# Risha.net
KiCad netlist of a schematic drawn in EAGLE
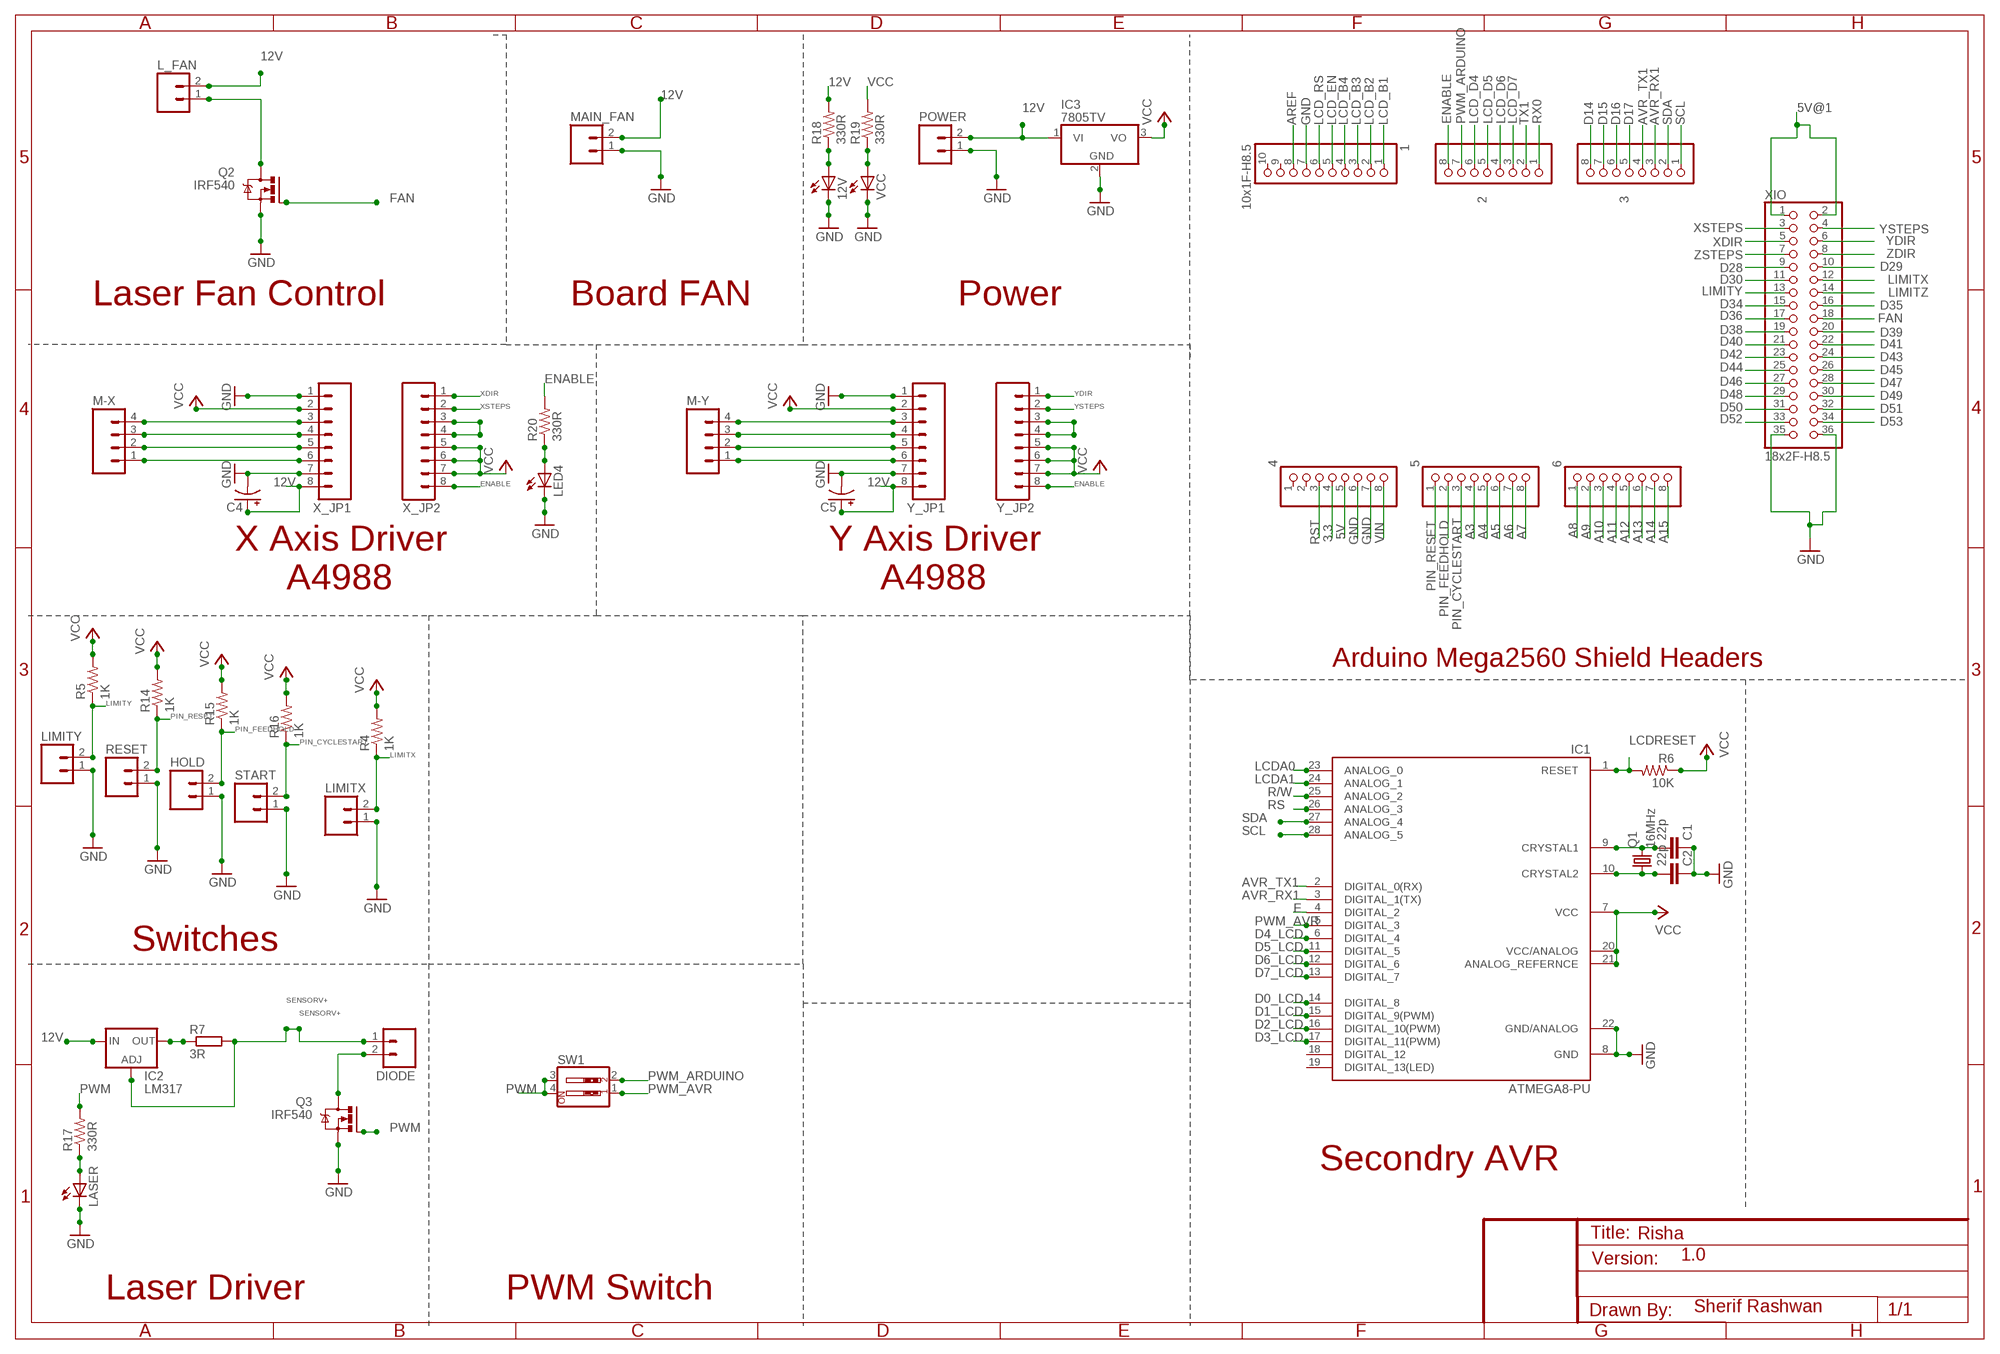
[diagram p0: schematic, sheet 1]

(export (version "E")
  (design (tool "Eeschema 10.0.6"))
  (components
    (comp (ref "1")
      (value "10x1F-H8.5")
      (footprint "eagle-import:1X10")
      (libsource (lib "eagle-import") (part "PINHD-1X10_ARD"))
    )
    (comp (ref "2")
      (value "8x1F-H8.5")
      (footprint "eagle-import:1X08")
      (libsource (lib "eagle-import") (part "PINHD-1X8"))
    )
    (comp (ref "3")
      (value "8x1F-H8.5")
      (footprint "eagle-import:1X08")
      (libsource (lib "eagle-import") (part "PINHD-1X8"))
    )
    (comp (ref "4")
      (value "8x1F-H8.5")
      (footprint "eagle-import:1X08")
      (libsource (lib "eagle-import") (part "PINHD-1X8"))
    )
    (comp (ref "5")
      (value "8x1F-H8.5")
      (footprint "eagle-import:1X08")
      (libsource (lib "eagle-import") (part "PINHD-1X8"))
    )
    (comp (ref "6")
      (value "8x1F-H8.5")
      (footprint "eagle-import:1X08")
      (libsource (lib "eagle-import") (part "PINHD-1X8"))
    )
    (comp (ref "12V")
      (value "LED3MM")
      (footprint "eagle-import:LED3MM")
      (libsource (lib "eagle-import") (part "LED3MM"))
    )
    (comp (ref "C1")
      (value "22p")
      (footprint "eagle-import:C2.5-2")
      (libsource (lib "eagle-import") (part "C2.5/2"))
    )
    (comp (ref "C2")
      (value "22p")
      (footprint "eagle-import:C2.5-2")
      (libsource (lib "eagle-import") (part "C2.5/2"))
    )
    (comp (ref "C4")
      (value "CAP_POLPTH2")
      (footprint "eagle-import:CPOL-RADIAL-10UF-25V")
      (libsource (lib "eagle-import") (part "CAP_POLPTH2"))
    )
    (comp (ref "C5")
      (value "CAP_POLPTH2")
      (footprint "eagle-import:CPOL-RADIAL-10UF-25V")
      (libsource (lib "eagle-import") (part "CAP_POLPTH2"))
    )
    (comp (ref "DIODE")
      (value "M02PTH")
      (footprint "eagle-import:1X02")
      (libsource (lib "eagle-import") (part "M02PTH"))
    )
    (comp (ref "HOLD")
      (value "M02PTH")
      (footprint "eagle-import:1X02")
      (libsource (lib "eagle-import") (part "M02PTH"))
    )
    (comp (ref "IC1")
      (value "ATMEGA8-PU")
      (footprint "eagle-import:DIL28-3")
      (libsource (lib "eagle-import") (part "ATMEGA8-PU"))
    )
    (comp (ref "IC2")
      (value "LM317")
      (footprint "eagle-import:TO3-K02")
      (libsource (lib "eagle-import") (part "LM317-TO3"))
    )
    (comp (ref "IC3")
      (value "7805TV")
      (footprint "eagle-import:TO220V")
      (libsource (lib "eagle-import") (part "78TV05"))
    )
    (comp (ref "LASER")
      (value "LED3MM")
      (footprint "eagle-import:LED3MM")
      (libsource (lib "eagle-import") (part "LED3MM"))
    )
    (comp (ref "LED4")
      (value "LED3MM")
      (footprint "eagle-import:LED3MM")
      (libsource (lib "eagle-import") (part "LED3MM"))
    )
    (comp (ref "LIMITX")
      (value "M02PTH")
      (footprint "eagle-import:1X02")
      (libsource (lib "eagle-import") (part "M02PTH"))
    )
    (comp (ref "LIMITY")
      (value "M02PTH")
      (footprint "eagle-import:1X02")
      (libsource (lib "eagle-import") (part "M02PTH"))
    )
    (comp (ref "L_FAN")
      (value "M02PTH")
      (footprint "eagle-import:1X02")
      (libsource (lib "eagle-import") (part "M02PTH"))
    )
    (comp (ref "M-X")
      (value "M04PTH")
      (footprint "eagle-import:1X04")
      (libsource (lib "eagle-import") (part "M04PTH"))
    )
    (comp (ref "M-Y")
      (value "M04PTH")
      (footprint "eagle-import:1X04")
      (libsource (lib "eagle-import") (part "M04PTH"))
    )
    (comp (ref "MAIN_FAN")
      (value "M02PTH")
      (footprint "eagle-import:1X02")
      (libsource (lib "eagle-import") (part "M02PTH"))
    )
    (comp (ref "POWER")
      (value "M02PTH")
      (footprint "eagle-import:1X02")
      (libsource (lib "eagle-import") (part "M02PTH"))
    )
    (comp (ref "Q1")
      (value "16MHz")
      (footprint "eagle-import:HC49US")
      (libsource (lib "eagle-import") (part "CRYSTALHC49US"))
    )
    (comp (ref "Q2")
      (value "IRF540")
      (footprint "eagle-import:TO220BV")
      (libsource (lib "eagle-import") (part "IRF540"))
    )
    (comp (ref "Q3")
      (value "IRF540")
      (footprint "eagle-import:TO220BV")
      (libsource (lib "eagle-import") (part "IRF540"))
    )
    (comp (ref "R4")
      (value "1K")
      (footprint "eagle-import:1_6W-RES")
      (libsource (lib "eagle-import") (part "RESISTORPTH-1/6W"))
    )
    (comp (ref "R5")
      (value "1K")
      (footprint "eagle-import:1_6W-RES")
      (libsource (lib "eagle-import") (part "RESISTORPTH-1/6W"))
    )
    (comp (ref "R6")
      (value "10K")
      (footprint "eagle-import:1_6W-RES")
      (libsource (lib "eagle-import") (part "RESISTORPTH-1/6W"))
    )
    (comp (ref "R7")
      (value "3R")
      (footprint "eagle-import:0309_12")
      (libsource (lib "eagle-import") (part "R-EU_0309/12"))
    )
    (comp (ref "R14")
      (value "1K")
      (footprint "eagle-import:1_6W-RES")
      (libsource (lib "eagle-import") (part "RESISTORPTH-1/6W"))
    )
    (comp (ref "R15")
      (value "1K")
      (footprint "eagle-import:1_6W-RES")
      (libsource (lib "eagle-import") (part "RESISTORPTH-1/6W"))
    )
    (comp (ref "R16")
      (value "1K")
      (footprint "eagle-import:1_6W-RES")
      (libsource (lib "eagle-import") (part "RESISTORPTH-1/6W"))
    )
    (comp (ref "R17")
      (value "330R")
      (footprint "eagle-import:1_6W-RES")
      (libsource (lib "eagle-import") (part "RESISTORPTH-1/6W"))
    )
    (comp (ref "R18")
      (value "330R")
      (footprint "eagle-import:1_6W-RES")
      (libsource (lib "eagle-import") (part "RESISTORPTH-1/6W"))
    )
    (comp (ref "R19")
      (value "330R")
      (footprint "eagle-import:1_6W-RES")
      (libsource (lib "eagle-import") (part "RESISTORPTH-1/6W"))
    )
    (comp (ref "R20")
      (value "330R")
      (footprint "eagle-import:1_6W-RES")
      (libsource (lib "eagle-import") (part "RESISTORPTH-1/6W"))
    )
    (comp (ref "RESET")
      (value "M02PTH")
      (footprint "eagle-import:1X02")
      (libsource (lib "eagle-import") (part "M02PTH"))
    )
    (comp (ref "START")
      (value "M02PTH")
      (footprint "eagle-import:1X02")
      (libsource (lib "eagle-import") (part "M02PTH"))
    )
    (comp (ref "SW1")
      (value "SW_DIP-2")
      (footprint "eagle-import:EDG-02")
      (libsource (lib "eagle-import") (part "SW_DIP-2"))
    )
    (comp (ref "VCC")
      (value "LED3MM")
      (footprint "eagle-import:LED3MM")
      (libsource (lib "eagle-import") (part "LED3MM"))
    )
    (comp (ref "XIO")
      (value "18x2F-H8.5")
      (footprint "eagle-import:2X18")
      (libsource (lib "eagle-import") (part "PINHD-2X18"))
    )
    (comp (ref "X_JP1")
      (value "M08")
      (footprint "eagle-import:1X08")
      (libsource (lib "eagle-import") (part "M08"))
    )
    (comp (ref "X_JP2")
      (value "M08")
      (footprint "eagle-import:1X08")
      (libsource (lib "eagle-import") (part "M08"))
    )
    (comp (ref "Y_JP1")
      (value "M08")
      (footprint "eagle-import:1X08")
      (libsource (lib "eagle-import") (part "M08"))
    )
    (comp (ref "Y_JP2")
      (value "M08")
      (footprint "eagle-import:1X08")
      (libsource (lib "eagle-import") (part "M08"))
    )
  )
  (nets
    (net (code "1") (name "/3.3") (class "Default")
      (node (ref "4") (pin "4") (pinfunction "4_4") (pintype "passive"))
    )
    (net (code "2") (name "/5V") (class "Default")
      (node (ref "4") (pin "5") (pinfunction "5_5") (pintype "passive"))
    )
    (net (code "3") (name "/5V@1") (class "Default")
      (node (ref "XIO") (pin "1") (pinfunction "1_1") (pintype "passive"))
      (node (ref "XIO") (pin "2") (pinfunction "2_2") (pintype "passive"))
    )
    (net (code "4") (name "/12V") (class "Default")
      (node (ref "C4") (pin "1") (pinfunction "+_1") (pintype "passive"))
      (node (ref "C5") (pin "1") (pinfunction "+_1") (pintype "passive"))
      (node (ref "IC2") (pin "1") (pinfunction "IN_1") (pintype "input"))
      (node (ref "IC3") (pin "1") (pinfunction "VI_1") (pintype "input"))
      (node (ref "L_FAN") (pin "2") (pinfunction "2_2") (pintype "passive"))
      (node (ref "MAIN_FAN") (pin "2") (pinfunction "2_2") (pintype "passive"))
      (node (ref "POWER") (pin "2") (pinfunction "2_2") (pintype "passive"))
      (node (ref "R18") (pin "2") (pinfunction "2_2") (pintype "passive"))
      (node (ref "X_JP1") (pin "8") (pinfunction "8_8") (pintype "passive"))
      (node (ref "Y_JP1") (pin "8") (pinfunction "8_8") (pintype "passive"))
    )
    (net (code "5") (name "/A3") (class "Default")
      (node (ref "5") (pin "4") (pinfunction "4_4") (pintype "passive"))
    )
    (net (code "6") (name "/A4") (class "Default")
      (node (ref "5") (pin "5") (pinfunction "5_5") (pintype "passive"))
    )
    (net (code "7") (name "/A5") (class "Default")
      (node (ref "5") (pin "6") (pinfunction "6_6") (pintype "passive"))
    )
    (net (code "8") (name "/A6") (class "Default")
      (node (ref "5") (pin "7") (pinfunction "7_7") (pintype "passive"))
    )
    (net (code "9") (name "/A7") (class "Default")
      (node (ref "5") (pin "8") (pinfunction "8_8") (pintype "passive"))
    )
    (net (code "10") (name "/A8") (class "Default")
      (node (ref "6") (pin "1") (pinfunction "1_1") (pintype "passive"))
    )
    (net (code "11") (name "/A9") (class "Default")
      (node (ref "6") (pin "2") (pinfunction "2_2") (pintype "passive"))
    )
    (net (code "12") (name "/A10") (class "Default")
      (node (ref "6") (pin "3") (pinfunction "3_3") (pintype "passive"))
    )
    (net (code "13") (name "/A11") (class "Default")
      (node (ref "6") (pin "4") (pinfunction "4_4") (pintype "passive"))
    )
    (net (code "14") (name "/A12") (class "Default")
      (node (ref "6") (pin "5") (pinfunction "5_5") (pintype "passive"))
    )
    (net (code "15") (name "/A13") (class "Default")
      (node (ref "6") (pin "6") (pinfunction "6_6") (pintype "passive"))
    )
    (net (code "16") (name "/A14") (class "Default")
      (node (ref "6") (pin "7") (pinfunction "7_7") (pintype "passive"))
    )
    (net (code "17") (name "/A15") (class "Default")
      (node (ref "6") (pin "8") (pinfunction "8_8") (pintype "passive"))
    )
    (net (code "18") (name "/AREF") (class "Default")
      (node (ref "1") (pin "8") (pinfunction "8_8") (pintype "passive"))
    )
    (net (code "19") (name "/AVR_RX1") (class "Default")
      (node (ref "3") (pin "3") (pinfunction "3_3") (pintype "passive"))
      (node (ref "IC1") (pin "3") (pinfunction "DIGITAL_1(TX)_3") (pintype "bidirectional"))
    )
    (net (code "20") (name "/AVR_TX1") (class "Default")
      (node (ref "3") (pin "4") (pinfunction "4_4") (pintype "passive"))
      (node (ref "IC1") (pin "2") (pinfunction "DIGITAL_0(RX)_2") (pintype "bidirectional"))
    )
    (net (code "21") (name "/D0_LCD") (class "Default")
      (node (ref "IC1") (pin "14") (pinfunction "DIGITAL_8_14") (pintype "bidirectional"))
    )
    (net (code "22") (name "/D1_LCD") (class "Default")
      (node (ref "IC1") (pin "15") (pinfunction "DIGITAL_9(PWM)_15") (pintype "bidirectional"))
    )
    (net (code "23") (name "/D2_LCD") (class "Default")
      (node (ref "IC1") (pin "16") (pinfunction "DIGITAL_10(PWM)_16") (pintype "bidirectional"))
    )
    (net (code "24") (name "/D3_LCD") (class "Default")
      (node (ref "IC1") (pin "17") (pinfunction "DIGITAL_11(PWM)_17") (pintype "bidirectional"))
    )
    (net (code "25") (name "/D4_LCD") (class "Default")
      (node (ref "IC1") (pin "6") (pinfunction "DIGITAL_4_6") (pintype "bidirectional"))
    )
    (net (code "26") (name "/D5_LCD") (class "Default")
      (node (ref "IC1") (pin "11") (pinfunction "DIGITAL_5_11") (pintype "bidirectional"))
    )
    (net (code "27") (name "/D6_LCD") (class "Default")
      (node (ref "IC1") (pin "12") (pinfunction "DIGITAL_6_12") (pintype "bidirectional"))
    )
    (net (code "28") (name "/D7_LCD") (class "Default")
      (node (ref "IC1") (pin "13") (pinfunction "DIGITAL_7_13") (pintype "bidirectional"))
    )
    (net (code "29") (name "/D14") (class "Default")
      (node (ref "3") (pin "8") (pinfunction "8_8") (pintype "passive"))
    )
    (net (code "30") (name "/D15") (class "Default")
      (node (ref "3") (pin "7") (pinfunction "7_7") (pintype "passive"))
    )
    (net (code "31") (name "/D16") (class "Default")
      (node (ref "3") (pin "6") (pinfunction "6_6") (pintype "passive"))
    )
    (net (code "32") (name "/D17") (class "Default")
      (node (ref "3") (pin "5") (pinfunction "5_5") (pintype "passive"))
    )
    (net (code "33") (name "/D28") (class "Default")
      (node (ref "XIO") (pin "9") (pinfunction "9_9") (pintype "passive"))
    )
    (net (code "34") (name "/D29") (class "Default")
      (node (ref "XIO") (pin "10") (pinfunction "10_10") (pintype "passive"))
    )
    (net (code "35") (name "/D30") (class "Default")
      (node (ref "XIO") (pin "11") (pinfunction "11_11") (pintype "passive"))
    )
    (net (code "36") (name "/D34") (class "Default")
      (node (ref "XIO") (pin "15") (pinfunction "15_15") (pintype "passive"))
    )
    (net (code "37") (name "/D35") (class "Default")
      (node (ref "XIO") (pin "16") (pinfunction "16_16") (pintype "passive"))
    )
    (net (code "38") (name "/D36") (class "Default")
      (node (ref "XIO") (pin "17") (pinfunction "17_17") (pintype "passive"))
    )
    (net (code "39") (name "/D38") (class "Default")
      (node (ref "XIO") (pin "19") (pinfunction "19_19") (pintype "passive"))
    )
    (net (code "40") (name "/D39") (class "Default")
      (node (ref "XIO") (pin "20") (pinfunction "20_20") (pintype "passive"))
    )
    (net (code "41") (name "/D40") (class "Default")
      (node (ref "XIO") (pin "21") (pinfunction "21_21") (pintype "passive"))
    )
    (net (code "42") (name "/D41") (class "Default")
      (node (ref "XIO") (pin "22") (pinfunction "22_22") (pintype "passive"))
    )
    (net (code "43") (name "/D42") (class "Default")
      (node (ref "XIO") (pin "23") (pinfunction "23_23") (pintype "passive"))
    )
    (net (code "44") (name "/D43") (class "Default")
      (node (ref "XIO") (pin "24") (pinfunction "24_24") (pintype "passive"))
    )
    (net (code "45") (name "/D44") (class "Default")
      (node (ref "XIO") (pin "25") (pinfunction "25_25") (pintype "passive"))
    )
    (net (code "46") (name "/D45") (class "Default")
      (node (ref "XIO") (pin "26") (pinfunction "26_26") (pintype "passive"))
    )
    (net (code "47") (name "/D46") (class "Default")
      (node (ref "XIO") (pin "27") (pinfunction "27_27") (pintype "passive"))
    )
    (net (code "48") (name "/D47") (class "Default")
      (node (ref "XIO") (pin "28") (pinfunction "28_28") (pintype "passive"))
    )
    (net (code "49") (name "/D48") (class "Default")
      (node (ref "XIO") (pin "29") (pinfunction "29_29") (pintype "passive"))
    )
    (net (code "50") (name "/D49") (class "Default")
      (node (ref "XIO") (pin "30") (pinfunction "30_30") (pintype "passive"))
    )
    (net (code "51") (name "/D50") (class "Default")
      (node (ref "XIO") (pin "31") (pinfunction "31_31") (pintype "passive"))
    )
    (net (code "52") (name "/D51") (class "Default")
      (node (ref "XIO") (pin "32") (pinfunction "32_32") (pintype "passive"))
    )
    (net (code "53") (name "/D52") (class "Default")
      (node (ref "XIO") (pin "33") (pinfunction "33_33") (pintype "passive"))
    )
    (net (code "54") (name "/D53") (class "Default")
      (node (ref "XIO") (pin "34") (pinfunction "34_34") (pintype "passive"))
    )
    (net (code "55") (name "/E") (class "Default")
      (node (ref "IC1") (pin "4") (pinfunction "DIGITAL_2_4") (pintype "bidirectional"))
    )
    (net (code "56") (name "/ENABLE") (class "Default")
      (node (ref "2") (pin "8") (pinfunction "8_8") (pintype "passive"))
      (node (ref "R20") (pin "2") (pinfunction "2_2") (pintype "passive"))
      (node (ref "X_JP2") (pin "8") (pinfunction "8_8") (pintype "passive"))
      (node (ref "Y_JP2") (pin "8") (pinfunction "8_8") (pintype "passive"))
    )
    (net (code "57") (name "/FAN") (class "Default")
      (node (ref "Q2") (pin "G") (pinfunction "G_G") (pintype "passive"))
      (node (ref "XIO") (pin "18") (pinfunction "18_18") (pintype "passive"))
    )
    (net (code "58") (name "/LCDA0") (class "Default")
      (node (ref "IC1") (pin "23") (pinfunction "ANALOG_0_23") (pintype "bidirectional"))
    )
    (net (code "59") (name "/LCDA1") (class "Default")
      (node (ref "IC1") (pin "24") (pinfunction "ANALOG_1_24") (pintype "bidirectional"))
    )
    (net (code "60") (name "/LCDRESET") (class "Default")
      (node (ref "IC1") (pin "1") (pinfunction "RESET_1") (pintype "bidirectional"))
      (node (ref "R6") (pin "2") (pinfunction "2_2") (pintype "passive"))
    )
    (net (code "61") (name "/LCD_B1") (class "Default")
      (node (ref "1") (pin "1") (pinfunction "1_1") (pintype "passive"))
    )
    (net (code "62") (name "/LCD_B2") (class "Default")
      (node (ref "1") (pin "2") (pinfunction "2_2") (pintype "passive"))
    )
    (net (code "63") (name "/LCD_B3") (class "Default")
      (node (ref "1") (pin "3") (pinfunction "3_3") (pintype "passive"))
    )
    (net (code "64") (name "/LCD_B4") (class "Default")
      (node (ref "1") (pin "4") (pinfunction "4_4") (pintype "passive"))
    )
    (net (code "65") (name "/LCD_D4") (class "Default")
      (node (ref "2") (pin "6") (pinfunction "6_6") (pintype "passive"))
    )
    (net (code "66") (name "/LCD_D5") (class "Default")
      (node (ref "2") (pin "5") (pinfunction "5_5") (pintype "passive"))
    )
    (net (code "67") (name "/LCD_D6") (class "Default")
      (node (ref "2") (pin "4") (pinfunction "4_4") (pintype "passive"))
    )
    (net (code "68") (name "/LCD_D7") (class "Default")
      (node (ref "2") (pin "3") (pinfunction "3_3") (pintype "passive"))
    )
    (net (code "69") (name "/LCD_EN") (class "Default")
      (node (ref "1") (pin "5") (pinfunction "5_5") (pintype "passive"))
    )
    (net (code "70") (name "/LCD_RS") (class "Default")
      (node (ref "1") (pin "6") (pinfunction "6_6") (pintype "passive"))
    )
    (net (code "71") (name "/LIMITX") (class "Default")
      (node (ref "LIMITX") (pin "2") (pinfunction "2_2") (pintype "passive"))
      (node (ref "R4") (pin "1") (pinfunction "1_1") (pintype "passive"))
      (node (ref "XIO") (pin "12") (pinfunction "12_12") (pintype "passive"))
    )
    (net (code "72") (name "/LIMITY") (class "Default")
      (node (ref "LIMITY") (pin "2") (pinfunction "2_2") (pintype "passive"))
      (node (ref "R5") (pin "1") (pinfunction "1_1") (pintype "passive"))
      (node (ref "XIO") (pin "13") (pinfunction "13_13") (pintype "passive"))
    )
    (net (code "73") (name "/LIMITZ") (class "Default")
      (node (ref "XIO") (pin "14") (pinfunction "14_14") (pintype "passive"))
    )
    (net (code "74") (name "/PIN_CYCLESTART") (class "Default")
      (node (ref "5") (pin "3") (pinfunction "3_3") (pintype "passive"))
      (node (ref "R16") (pin "1") (pinfunction "1_1") (pintype "passive"))
      (node (ref "START") (pin "2") (pinfunction "2_2") (pintype "passive"))
    )
    (net (code "75") (name "/PIN_FEEDHOLD") (class "Default")
      (node (ref "5") (pin "2") (pinfunction "2_2") (pintype "passive"))
      (node (ref "HOLD") (pin "2") (pinfunction "2_2") (pintype "passive"))
      (node (ref "R15") (pin "1") (pinfunction "1_1") (pintype "passive"))
    )
    (net (code "76") (name "/PIN_RESET") (class "Default")
      (node (ref "5") (pin "1") (pinfunction "1_1") (pintype "passive"))
      (node (ref "R14") (pin "1") (pinfunction "1_1") (pintype "passive"))
      (node (ref "RESET") (pin "2") (pinfunction "2_2") (pintype "passive"))
    )
    (net (code "77") (name "/PWM") (class "Default")
      (node (ref "Q3") (pin "G") (pinfunction "G_G") (pintype "passive"))
      (node (ref "R17") (pin "2") (pinfunction "2_2") (pintype "passive"))
      (node (ref "SW1") (pin "3") (pinfunction "3_3") (pintype "passive"))
      (node (ref "SW1") (pin "4") (pinfunction "4_4") (pintype "passive"))
    )
    (net (code "78") (name "/PWM_ARDUINO") (class "Default")
      (node (ref "2") (pin "7") (pinfunction "7_7") (pintype "passive"))
      (node (ref "SW1") (pin "2") (pinfunction "2_2") (pintype "passive"))
    )
    (net (code "79") (name "/PWM_AVR") (class "Default")
      (node (ref "IC1") (pin "5") (pinfunction "DIGITAL_3_5") (pintype "bidirectional"))
      (node (ref "SW1") (pin "1") (pinfunction "1_1") (pintype "passive"))
    )
    (net (code "80") (name "/RS") (class "Default")
      (node (ref "IC1") (pin "26") (pinfunction "ANALOG_3_26") (pintype "bidirectional"))
    )
    (net (code "81") (name "/RST") (class "Default")
      (node (ref "4") (pin "3") (pinfunction "3_3") (pintype "passive"))
    )
    (net (code "82") (name "/RX0") (class "Default")
      (node (ref "2") (pin "1") (pinfunction "1_1") (pintype "passive"))
    )
    (net (code "83") (name "/R{slash}W") (class "Default")
      (node (ref "IC1") (pin "25") (pinfunction "ANALOG_2_25") (pintype "bidirectional"))
    )
    (net (code "84") (name "/SCL") (class "Default")
      (node (ref "3") (pin "1") (pinfunction "1_1") (pintype "passive"))
      (node (ref "IC1") (pin "28") (pinfunction "ANALOG_5_28") (pintype "bidirectional"))
    )
    (net (code "85") (name "/SDA") (class "Default")
      (node (ref "3") (pin "2") (pinfunction "2_2") (pintype "passive"))
      (node (ref "IC1") (pin "27") (pinfunction "ANALOG_4_27") (pintype "bidirectional"))
    )
    (net (code "86") (name "/SENSORV+") (class "Default")
      (node (ref "DIODE") (pin "1") (pinfunction "1_1") (pintype "passive"))
      (node (ref "IC2") (pin "2") (pinfunction "ADJ_2") (pintype "input"))
      (node (ref "R7") (pin "2") (pinfunction "2_2") (pintype "passive"))
    )
    (net (code "87") (name "/TX1") (class "Default")
      (node (ref "2") (pin "2") (pinfunction "2_2") (pintype "passive"))
    )
    (net (code "88") (name "/VIN") (class "Default")
      (node (ref "4") (pin "8") (pinfunction "8_8") (pintype "passive"))
    )
    (net (code "89") (name "/XDIR") (class "Default")
      (node (ref "XIO") (pin "5") (pinfunction "5_5") (pintype "passive"))
      (node (ref "X_JP2") (pin "1") (pinfunction "1_1") (pintype "passive"))
    )
    (net (code "90") (name "/XSTEPS") (class "Default")
      (node (ref "XIO") (pin "3") (pinfunction "3_3") (pintype "passive"))
      (node (ref "X_JP2") (pin "2") (pinfunction "2_2") (pintype "passive"))
    )
    (net (code "91") (name "/YDIR") (class "Default")
      (node (ref "XIO") (pin "6") (pinfunction "6_6") (pintype "passive"))
      (node (ref "Y_JP2") (pin "1") (pinfunction "1_1") (pintype "passive"))
    )
    (net (code "92") (name "/YSTEPS") (class "Default")
      (node (ref "XIO") (pin "4") (pinfunction "4_4") (pintype "passive"))
      (node (ref "Y_JP2") (pin "2") (pinfunction "2_2") (pintype "passive"))
    )
    (net (code "93") (name "/ZDIR") (class "Default")
      (node (ref "XIO") (pin "8") (pinfunction "8_8") (pintype "passive"))
    )
    (net (code "94") (name "/ZSTEPS") (class "Default")
      (node (ref "XIO") (pin "7") (pinfunction "7_7") (pintype "passive"))
    )
    (net (code "95") (name "GND") (class "Default")
      (node (ref "1") (pin "7") (pinfunction "7_7") (pintype "passive"))
      (node (ref "12V") (pin "K") (pinfunction "C_K") (pintype "passive"))
      (node (ref "4") (pin "6") (pinfunction "6_6") (pintype "passive"))
      (node (ref "4") (pin "7") (pinfunction "7_7") (pintype "passive"))
      (node (ref "C1") (pin "1") (pinfunction "1_1") (pintype "passive"))
      (node (ref "C2") (pin "1") (pinfunction "1_1") (pintype "passive"))
      (node (ref "C4") (pin "2") (pinfunction "-_2") (pintype "passive"))
      (node (ref "C5") (pin "2") (pinfunction "-_2") (pintype "passive"))
      (node (ref "HOLD") (pin "1") (pinfunction "1_1") (pintype "passive"))
      (node (ref "IC1") (pin "22") (pinfunction "GND/ANALOG_22") (pintype "power_in"))
      (node (ref "IC1") (pin "8") (pinfunction "GND_8") (pintype "power_in"))
      (node (ref "IC3") (pin "2") (pinfunction "GND_2") (pintype "passive"))
      (node (ref "LASER") (pin "K") (pinfunction "C_K") (pintype "passive"))
      (node (ref "LED4") (pin "K") (pinfunction "C_K") (pintype "passive"))
      (node (ref "LIMITX") (pin "1") (pinfunction "1_1") (pintype "passive"))
      (node (ref "LIMITY") (pin "1") (pinfunction "1_1") (pintype "passive"))
      (node (ref "MAIN_FAN") (pin "1") (pinfunction "1_1") (pintype "passive"))
      (node (ref "POWER") (pin "1") (pinfunction "1_1") (pintype "passive"))
      (node (ref "Q2") (pin "S") (pinfunction "S_S") (pintype "passive"))
      (node (ref "Q3") (pin "S") (pinfunction "S_S") (pintype "passive"))
      (node (ref "RESET") (pin "1") (pinfunction "1_1") (pintype "passive"))
      (node (ref "START") (pin "1") (pinfunction "1_1") (pintype "passive"))
      (node (ref "VCC") (pin "K") (pinfunction "C_K") (pintype "passive"))
      (node (ref "XIO") (pin "35") (pinfunction "35_35") (pintype "passive"))
      (node (ref "XIO") (pin "36") (pinfunction "36_36") (pintype "passive"))
      (node (ref "X_JP1") (pin "1") (pinfunction "1_1") (pintype "passive"))
      (node (ref "X_JP1") (pin "7") (pinfunction "7_7") (pintype "passive"))
      (node (ref "Y_JP1") (pin "1") (pinfunction "1_1") (pintype "passive"))
      (node (ref "Y_JP1") (pin "7") (pinfunction "7_7") (pintype "passive"))
    )
    (net (code "96") (name "Net-(12V-PadA)") (class "Default")
      (node (ref "12V") (pin "A") (pinfunction "A_A") (pintype "passive"))
      (node (ref "R18") (pin "1") (pinfunction "1_1") (pintype "passive"))
    )
    (net (code "97") (name "Net-(DIODE-Pad2)") (class "Default")
      (node (ref "DIODE") (pin "2") (pinfunction "2_2") (pintype "passive"))
      (node (ref "Q3") (pin "D") (pinfunction "D_D") (pintype "passive"))
    )
    (net (code "98") (name "Net-(IC1-CRYSTAL1)") (class "Default")
      (node (ref "C1") (pin "2") (pinfunction "2_2") (pintype "passive"))
      (node (ref "IC1") (pin "9") (pinfunction "CRYSTAL1_9") (pintype "bidirectional"))
      (node (ref "Q1") (pin "2") (pinfunction "2_2") (pintype "passive"))
    )
    (net (code "99") (name "Net-(IC1-CRYSTAL2)") (class "Default")
      (node (ref "C2") (pin "2") (pinfunction "2_2") (pintype "passive"))
      (node (ref "IC1") (pin "10") (pinfunction "CRYSTAL2_10") (pintype "bidirectional"))
      (node (ref "Q1") (pin "1") (pinfunction "1_1") (pintype "passive"))
    )
    (net (code "100") (name "Net-(IC2-OUT)") (class "Default")
      (node (ref "IC2") (pin "3") (pinfunction "OUT_3") (pintype "passive"))
      (node (ref "R7") (pin "1") (pinfunction "1_1") (pintype "passive"))
    )
    (net (code "101") (name "Net-(LASER-PadA)") (class "Default")
      (node (ref "LASER") (pin "A") (pinfunction "A_A") (pintype "passive"))
      (node (ref "R17") (pin "1") (pinfunction "1_1") (pintype "passive"))
    )
    (net (code "102") (name "Net-(LED4-PadA)") (class "Default")
      (node (ref "LED4") (pin "A") (pinfunction "A_A") (pintype "passive"))
      (node (ref "R20") (pin "1") (pinfunction "1_1") (pintype "passive"))
    )
    (net (code "103") (name "Net-(L_FAN-Pad1)") (class "Default")
      (node (ref "L_FAN") (pin "1") (pinfunction "1_1") (pintype "passive"))
      (node (ref "Q2") (pin "D") (pinfunction "D_D") (pintype "passive"))
    )
    (net (code "104") (name "Net-(M-X-Pad1)") (class "Default")
      (node (ref "M-X") (pin "1") (pinfunction "1_1") (pintype "passive"))
      (node (ref "X_JP1") (pin "6") (pinfunction "6_6") (pintype "passive"))
    )
    (net (code "105") (name "Net-(M-X-Pad2)") (class "Default")
      (node (ref "M-X") (pin "2") (pinfunction "2_2") (pintype "passive"))
      (node (ref "X_JP1") (pin "5") (pinfunction "5_5") (pintype "passive"))
    )
    (net (code "106") (name "Net-(M-X-Pad3)") (class "Default")
      (node (ref "M-X") (pin "3") (pinfunction "3_3") (pintype "passive"))
      (node (ref "X_JP1") (pin "4") (pinfunction "4_4") (pintype "passive"))
    )
    (net (code "107") (name "Net-(M-X-Pad4)") (class "Default")
      (node (ref "M-X") (pin "4") (pinfunction "4_4") (pintype "passive"))
      (node (ref "X_JP1") (pin "3") (pinfunction "3_3") (pintype "passive"))
    )
    (net (code "108") (name "Net-(M-Y-Pad1)") (class "Default")
      (node (ref "M-Y") (pin "1") (pinfunction "1_1") (pintype "passive"))
      (node (ref "Y_JP1") (pin "6") (pinfunction "6_6") (pintype "passive"))
    )
    (net (code "109") (name "Net-(M-Y-Pad2)") (class "Default")
      (node (ref "M-Y") (pin "2") (pinfunction "2_2") (pintype "passive"))
      (node (ref "Y_JP1") (pin "5") (pinfunction "5_5") (pintype "passive"))
    )
    (net (code "110") (name "Net-(M-Y-Pad3)") (class "Default")
      (node (ref "M-Y") (pin "3") (pinfunction "3_3") (pintype "passive"))
      (node (ref "Y_JP1") (pin "4") (pinfunction "4_4") (pintype "passive"))
    )
    (net (code "111") (name "Net-(M-Y-Pad4)") (class "Default")
      (node (ref "M-Y") (pin "4") (pinfunction "4_4") (pintype "passive"))
      (node (ref "Y_JP1") (pin "3") (pinfunction "3_3") (pintype "passive"))
    )
    (net (code "112") (name "Net-(R19-Pad1)") (class "Default")
      (node (ref "R19") (pin "1") (pinfunction "1_1") (pintype "passive"))
      (node (ref "VCC") (pin "A") (pinfunction "A_A") (pintype "passive"))
    )
    (net (code "113") (name "Net-(X_JP2-Pad3)") (class "Default")
      (node (ref "X_JP2") (pin "3") (pinfunction "3_3") (pintype "passive"))
      (node (ref "X_JP2") (pin "4") (pinfunction "4_4") (pintype "passive"))
    )
    (net (code "114") (name "Net-(Y_JP2-Pad3)") (class "Default")
      (node (ref "Y_JP2") (pin "3") (pinfunction "3_3") (pintype "passive"))
      (node (ref "Y_JP2") (pin "4") (pinfunction "4_4") (pintype "passive"))
    )
    (net (code "115") (name "VCC") (class "Default")
      (node (ref "IC1") (pin "20") (pinfunction "VCC/ANALOG_20") (pintype "passive"))
      (node (ref "IC1") (pin "21") (pinfunction "ANALOG_REFERNCE_21") (pintype "passive"))
      (node (ref "IC1") (pin "7") (pinfunction "VCC_7") (pintype "power_in"))
      (node (ref "IC3") (pin "3") (pinfunction "VO_3") (pintype "passive"))
      (node (ref "R14") (pin "2") (pinfunction "2_2") (pintype "passive"))
      (node (ref "R15") (pin "2") (pinfunction "2_2") (pintype "passive"))
      (node (ref "R16") (pin "2") (pinfunction "2_2") (pintype "passive"))
      (node (ref "R19") (pin "2") (pinfunction "2_2") (pintype "passive"))
      (node (ref "R4") (pin "2") (pinfunction "2_2") (pintype "passive"))
      (node (ref "R5") (pin "2") (pinfunction "2_2") (pintype "passive"))
      (node (ref "R6") (pin "1") (pinfunction "1_1") (pintype "passive"))
      (node (ref "X_JP1") (pin "2") (pinfunction "2_2") (pintype "passive"))
      (node (ref "X_JP2") (pin "5") (pinfunction "5_5") (pintype "passive"))
      (node (ref "X_JP2") (pin "6") (pinfunction "6_6") (pintype "passive"))
      (node (ref "X_JP2") (pin "7") (pinfunction "7_7") (pintype "passive"))
      (node (ref "Y_JP1") (pin "2") (pinfunction "2_2") (pintype "passive"))
      (node (ref "Y_JP2") (pin "5") (pinfunction "5_5") (pintype "passive"))
      (node (ref "Y_JP2") (pin "6") (pinfunction "6_6") (pintype "passive"))
      (node (ref "Y_JP2") (pin "7") (pinfunction "7_7") (pintype "passive"))
    )
    (net (code "116") (name "unconnected-(1-Pad9)") (class "Default")
      (node (ref "1") (pin "9") (pinfunction "9_9") (pintype "passive"))
    )
    (net (code "117") (name "unconnected-(1-Pad10)") (class "Default")
      (node (ref "1") (pin "10") (pinfunction "10_10") (pintype "passive"))
    )
    (net (code "118") (name "unconnected-(4-Pad1)") (class "Default")
      (node (ref "4") (pin "1") (pinfunction "1_1") (pintype "passive"))
    )
    (net (code "119") (name "unconnected-(4-Pad2)") (class "Default")
      (node (ref "4") (pin "2") (pinfunction "2_2") (pintype "passive"))
    )
    (net (code "120") (name "unconnected-(IC1-DIGITAL_12-Pad18)") (class "Default")
      (node (ref "IC1") (pin "18") (pinfunction "DIGITAL_12_18") (pintype "bidirectional"))
    )
    (net (code "121") (name "unconnected-(IC1-DIGITAL_13(LED)-Pad19)") (class "Default")
      (node (ref "IC1") (pin "19") (pinfunction "DIGITAL_13(LED)_19") (pintype "bidirectional"))
    )
  )
)
